# interface.net
KiCad netlist of a schematic drawn in Altium Designer
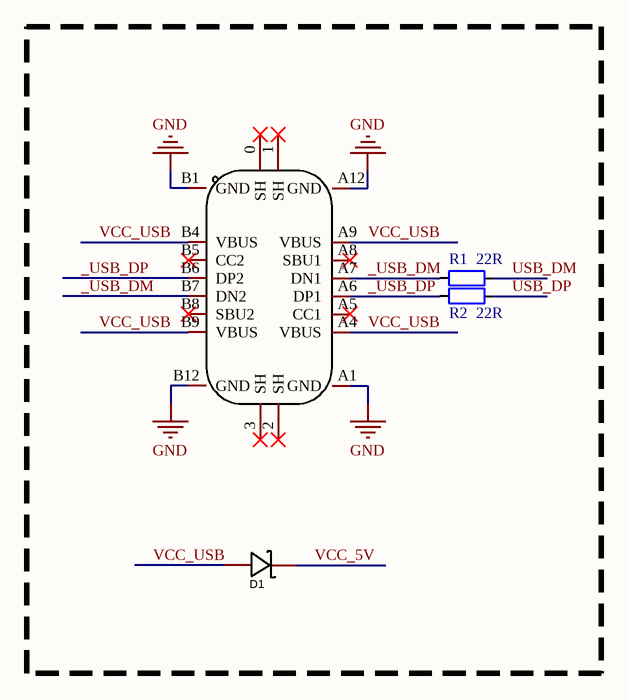
[diagram p0: interface.SchDoc]

(export (version "E")
  (design (tool "Eeschema 10.0.6"))
  (components
    (comp (ref "D1")
      (value "B5819WS")
      (footprint "SOD-323_L1.8-W1.3-LS2.5-RD")
      (fields (field (name "MANUFACTURER") "CJ(江苏长电/长晶)"))
      (libsource (lib "Other") (part "B5819WS"))
    )
    (comp (ref "R1") (value "22R") (footprint "R0603") (libsource (lib "vesc6") (part "R0603")))
    (comp (ref "R2") (value "22R") (footprint "R0603") (libsource (lib "vesc6") (part "R0603")))
    (comp (ref "USBC1")
      (value "TYPE-C-31-M-12")
      (footprint "Type-C-TOP")
      (fields (field (name "MANUFACTURER") "韩国韩荣"))
      (libsource (lib "vesc6") (part "TYPE-C-31-M-12"))
    )
  )
  (nets
    (net (code "1") (name "/USB_DM") (class "Default")
      (node (ref "R1") (pin "2") (pinfunction "2_2") (pintype "passive"))
    )
    (net (code "2") (name "/USB_DP") (class "Default")
      (node (ref "R2") (pin "2") (pinfunction "2_2") (pintype "passive"))
    )
    (net (code "3") (name "/VCC_5V") (class "Default")
      (node (ref "D1") (pin "1") (pinfunction "K_1") (pintype "passive"))
    )
    (net (code "4") (name "/VCC_USB") (class "Default")
      (node (ref "D1") (pin "2") (pinfunction "A_2") (pintype "passive"))
      (node (ref "USBC1") (pin "A4") (pinfunction "VBUS_A4") (pintype "passive"))
      (node (ref "USBC1") (pin "A9") (pinfunction "VBUS_A9") (pintype "passive"))
      (node (ref "USBC1") (pin "B4") (pinfunction "VBUS_B4") (pintype "passive"))
      (node (ref "USBC1") (pin "B9") (pinfunction "VBUS_B9") (pintype "passive"))
    )
    (net (code "5") (name "/_USB_DM") (class "Default")
      (node (ref "R1") (pin "1") (pinfunction "1_1") (pintype "passive"))
      (node (ref "USBC1") (pin "A7") (pinfunction "DN1_A7") (pintype "passive"))
      (node (ref "USBC1") (pin "B7") (pinfunction "DN2_B7") (pintype "passive"))
    )
    (net (code "6") (name "/_USB_DP") (class "Default")
      (node (ref "R2") (pin "1") (pinfunction "1_1") (pintype "passive"))
      (node (ref "USBC1") (pin "A6") (pinfunction "DP1_A6") (pintype "passive"))
      (node (ref "USBC1") (pin "B6") (pinfunction "DP2_B6") (pintype "passive"))
    )
    (net (code "7") (name "GND") (class "Default")
      (node (ref "USBC1") (pin "A1") (pinfunction "GND_A1") (pintype "passive"))
      (node (ref "USBC1") (pin "A12") (pinfunction "GND_A12") (pintype "passive"))
      (node (ref "USBC1") (pin "B1") (pinfunction "GND_B1") (pintype "passive"))
      (node (ref "USBC1") (pin "B12") (pinfunction "GND_B12") (pintype "passive"))
    )
    (net (code "8") (name "unconnected-(USBC1-CC1-PadA5)") (class "Default")
      (node (ref "USBC1") (pin "A5") (pinfunction "CC1_A5") (pintype "passive+no_connect"))
    )
    (net (code "9") (name "unconnected-(USBC1-CC2-PadB5)") (class "Default")
      (node (ref "USBC1") (pin "B5") (pinfunction "CC2_B5") (pintype "passive+no_connect"))
    )
    (net (code "10") (name "unconnected-(USBC1-SBU1-PadA8)") (class "Default")
      (node (ref "USBC1") (pin "A8") (pinfunction "SBU1_A8") (pintype "passive+no_connect"))
    )
    (net (code "11") (name "unconnected-(USBC1-SBU2-PadB8)") (class "Default")
      (node (ref "USBC1") (pin "B8") (pinfunction "SBU2_B8") (pintype "passive+no_connect"))
    )
    (net (code "12") (name "unconnected-(USBC1-SH-Pad0)") (class "Default")
      (node (ref "USBC1") (pin "0") (pinfunction "SH_0") (pintype "passive+no_connect"))
    )
    (net (code "13") (name "unconnected-(USBC1-SH-Pad1)") (class "Default")
      (node (ref "USBC1") (pin "1") (pinfunction "SH_1") (pintype "passive+no_connect"))
    )
    (net (code "14") (name "unconnected-(USBC1-SH-Pad2)") (class "Default")
      (node (ref "USBC1") (pin "2") (pinfunction "SH_2") (pintype "passive+no_connect"))
    )
    (net (code "15") (name "unconnected-(USBC1-SH-Pad3)") (class "Default")
      (node (ref "USBC1") (pin "3") (pinfunction "SH_3") (pintype "passive+no_connect"))
    )
  )
)
